# SHEET3.net
KiCad netlist of a schematic drawn in Altium Designer
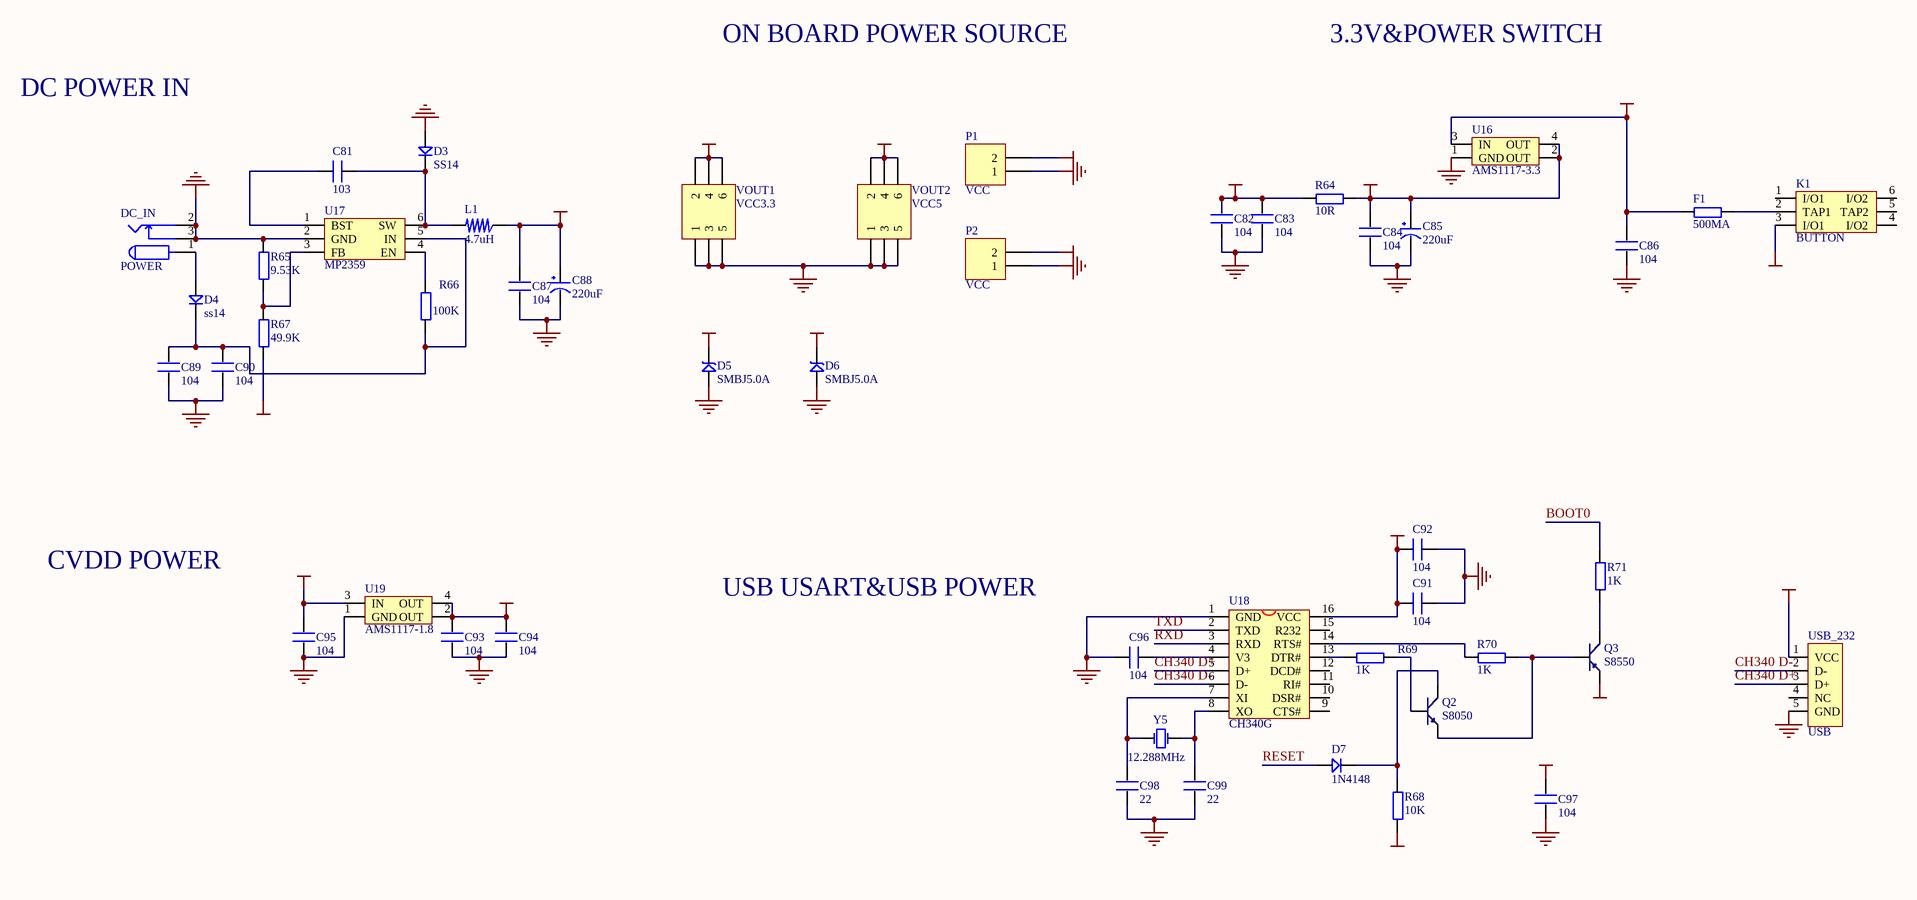
[diagram p0: SHEET3.SCHDOC]

(export (version "E")
  (design (tool "Eeschema 10.0.6"))
  (components
    (comp (ref "C81") (value "103") (footprint "0603P") (libsource (lib "战舰STM32开发板底板封装库") (part "C")))
    (comp (ref "C82") (value "104") (footprint "0603P") (libsource (lib "战舰STM32开发板底板封装库") (part "C")))
    (comp (ref "C83") (value "104") (footprint "0603P") (libsource (lib "战舰STM32开发板底板封装库") (part "C")))
    (comp (ref "C84") (value "104") (footprint "0603P") (libsource (lib "战舰STM32开发板底板封装库") (part "C")))
    (comp (ref "C85") (value "220uF") (footprint "CC6.56.5") (libsource (lib "战舰STM32开发板底板封装库") (part "CAP")))
    (comp (ref "C86") (value "104") (footprint "0603P") (libsource (lib "战舰STM32开发板底板封装库") (part "C")))
    (comp (ref "C87") (value "104") (footprint "0603P") (libsource (lib "战舰STM32开发板底板封装库") (part "C")))
    (comp (ref "C88") (value "220uF") (footprint "CC6.56.5") (libsource (lib "战舰STM32开发板底板封装库") (part "CAP")))
    (comp (ref "C89") (value "104") (footprint "0603P") (libsource (lib "战舰STM32开发板底板封装库") (part "C")))
    (comp (ref "C90") (value "104") (footprint "0603P") (libsource (lib "战舰STM32开发板底板封装库") (part "C")))
    (comp (ref "C91") (value "104") (footprint "0603P") (libsource (lib "战舰STM32开发板底板封装库") (part "C")))
    (comp (ref "C92") (value "104") (footprint "0603P") (libsource (lib "战舰STM32开发板底板封装库") (part "C")))
    (comp (ref "C93") (value "104") (footprint "0603P") (libsource (lib "战舰STM32开发板底板封装库") (part "C")))
    (comp (ref "C94") (value "104") (footprint "0603P") (libsource (lib "战舰STM32开发板底板封装库") (part "C")))
    (comp (ref "C95") (value "104") (footprint "0603P") (libsource (lib "战舰STM32开发板底板封装库") (part "C")))
    (comp (ref "C96") (value "104") (footprint "0603P") (libsource (lib "战舰STM32开发板底板封装库") (part "C")))
    (comp (ref "C97") (value "104") (footprint "0603P") (libsource (lib "战舰STM32开发板底板封装库") (part "C")))
    (comp (ref "C98") (value "22") (footprint "0603P") (libsource (lib "战舰STM32开发板底板封装库") (part "C")))
    (comp (ref "C99") (value "22") (footprint "0603P") (libsource (lib "战舰STM32开发板底板封装库") (part "C")))
    (comp (ref "D3") (value "SS14") (footprint "DIODE_SOP") (libsource (lib "战舰STM32开发板底板封装库") (part "D")))
    (comp (ref "D4") (value "ss14") (footprint "DIODE_SOP") (libsource (lib "战舰STM32开发板底板封装库") (part "D")))
    (comp (ref "D5")
      (value "SMBJ5.0A")
      (footprint "SMBJ")
      (description "TVS")
      (libsource (lib "战舰STM32开发板底板封装库") (part "SMBJ"))
    )
    (comp (ref "D6")
      (value "SMBJ5.0A")
      (footprint "SMBJ")
      (description "TVS")
      (libsource (lib "战舰STM32开发板底板封装库") (part "SMBJ"))
    )
    (comp (ref "D7") (value "1N4148") (footprint "DIODE_SOP") (libsource (lib "战舰STM32开发板底板封装库") (part "D")))
    (comp (ref "DC_IN") (value "POWER") (footprint "DC10B") (libsource (lib "战舰STM32开发板底板封装库") (part "POW")))
    (comp (ref "F1") (value "500MA") (footprint "0805") (libsource (lib "战舰STM32开发板底板封装库") (part "R")))
    (comp (ref "K1")
      (value "BUTTON")
      (footprint "BTN8.5*8.5")
      (libsource (lib "战舰STM32开发板底板封装库") (part "BUTTON"))
    )
    (comp (ref "L1") (value "4.7uH") (footprint "L_SOP74") (libsource (lib "战舰STM32开发板底板封装库") (part "L_SOP")))
    (comp (ref "P1")
      (value "VCC")
      (footprint "HDR1X2")
      (description "Header, 2-Pin")
      (fields (field (name "PUBLISHER") "Altium Limited"))
      (libsource (lib "ZD-STM32-ZOUYU") (part "Header 2"))
    )
    (comp (ref "P2")
      (value "VCC")
      (footprint "HDR1X2")
      (description "Header, 2-Pin")
      (fields (field (name "PUBLISHER") "Altium Limited"))
      (libsource (lib "ZD-STM32-ZOUYU") (part "Header 2"))
    )
    (comp (ref "Q2")
      (value "S8050")
      (footprint "SOT-23R")
      (description "8050/BCW846/BCW847")
      (libsource (lib "战舰STM32开发板底板封装库") (part "NPN"))
    )
    (comp (ref "Q3")
      (value "S8550")
      (footprint "SOT-23R")
      (description "8550/BCW68")
      (libsource (lib "战舰STM32开发板底板封装库") (part "PNP"))
    )
    (comp (ref "R64") (value "10R") (footprint "0603P") (libsource (lib "战舰STM32开发板底板封装库") (part "R")))
    (comp (ref "R65") (value "9.53K") (footprint "0603P") (libsource (lib "战舰STM32开发板底板封装库") (part "R")))
    (comp (ref "R66") (value "100K") (footprint "0603P") (libsource (lib "战舰STM32开发板底板封装库") (part "R")))
    (comp (ref "R67") (value "49.9K") (footprint "0603P") (libsource (lib "战舰STM32开发板底板封装库") (part "R")))
    (comp (ref "R68") (value "10K") (footprint "0603P") (libsource (lib "战舰STM32开发板底板封装库") (part "R")))
    (comp (ref "R69") (value "1K") (footprint "0603P") (libsource (lib "战舰STM32开发板底板封装库") (part "R")))
    (comp (ref "R70") (value "1K") (footprint "0603P") (libsource (lib "战舰STM32开发板底板封装库") (part "R")))
    (comp (ref "R71") (value "1K") (footprint "0603P") (libsource (lib "战舰STM32开发板底板封装库") (part "R")))
    (comp (ref "U16")
      (value "AMS1117-3.3")
      (footprint "AMS1117")
      (libsource (lib "战舰STM32开发板底板封装库") (part "AMS1117"))
    )
    (comp (ref "U17")
      (value "MP2359")
      (footprint "SOT-23-6")
      (description "DC DC Step Down IC")
      (libsource (lib "战舰STM32开发板底板封装库") (part "MP2359"))
    )
    (comp (ref "U18")
      (value "CH340G")
      (footprint "SOP16M")
      (description "USB2UART")
      (libsource (lib "战舰STM32开发板底板封装库") (part "CH340G"))
    )
    (comp (ref "U19")
      (value "AMS1117-1.8")
      (footprint "AMS1117")
      (libsource (lib "战舰STM32开发板底板封装库") (part "AMS1117"))
    )
    (comp (ref "USB_232")
      (value "USB")
      (footprint "USB/SM0.8-6H5")
      (libsource (lib "战舰STM32开发板底板封装库") (part "USB5"))
    )
    (comp (ref "VOUT1")
      (value "VCC3.3")
      (footprint "HDR2X3")
      (description "Header, 3-Pin, Dual row")
      (fields (field (name "PUBLISHER") "Altium Limited"))
      (libsource (lib "战舰STM32开发板底板封装库") (part "Header 3X2"))
    )
    (comp (ref "VOUT2")
      (value "VCC5")
      (footprint "HDR2X3")
      (description "Header, 3-Pin, Dual row")
      (fields (field (name "PUBLISHER") "Altium Limited"))
      (libsource (lib "战舰STM32开发板底板封装库") (part "Header 3X2"))
    )
    (comp (ref "Y5")
      (value "12.288MHz")
      (footprint "XTAL_US")
      (description "Crystal Oscillator")
      (fields (field (name "PUBLISHER") "Altium Limited"))
      (libsource (lib "战舰STM32开发板底板封装库") (part "XTAL_2"))
    )
  )
  (nets
    (net (code "1") (name "/BOOT0") (class "Default") (node (ref "R71") (pin "2") (pintype "passive")))
    (net (code "2") (name "/CH340 D+") (class "Default")
      (node (ref "U18") (pin "5") (pinfunction "D+_5") (pintype "passive"))
      (node (ref "USB_232") (pin "3") (pinfunction "D+_3") (pintype "passive"))
    )
    (net (code "3") (name "/CH340 D-") (class "Default")
      (node (ref "U18") (pin "6") (pinfunction "D-_6") (pintype "passive"))
      (node (ref "USB_232") (pin "2") (pinfunction "D-_2") (pintype "passive"))
    )
    (net (code "4") (name "/RESET") (class "Default") (node (ref "D7") (pin "1") (pintype "passive")))
    (net (code "5") (name "/RXD") (class "Default")
      (node (ref "U18") (pin "3") (pinfunction "RXD_3") (pintype "passive"))
    )
    (net (code "6") (name "/TXD") (class "Default")
      (node (ref "U18") (pin "2") (pinfunction "TXD_2") (pintype "passive"))
    )
    (net (code "7") (name "AVDD") (class "Default")
      (node (ref "C82") (pin "2") (pintype "passive"))
      (node (ref "C83") (pin "2") (pintype "passive"))
      (node (ref "R64") (pin "1") (pintype "passive"))
    )
    (net (code "8") (name "CVDD") (class "Default")
      (node (ref "C93") (pin "2") (pintype "passive"))
      (node (ref "C94") (pin "2") (pintype "passive"))
      (node (ref "U19") (pin "2") (pinfunction "OUT_2") (pintype "passive"))
      (node (ref "U19") (pin "4") (pinfunction "OUT_4") (pintype "passive"))
    )
    (net (code "9") (name "GND") (class "Default")
      (node (ref "C82") (pin "1") (pintype "passive"))
      (node (ref "C83") (pin "1") (pintype "passive"))
      (node (ref "C84") (pin "1") (pintype "passive"))
      (node (ref "C85") (pin "2") (pinfunction "GND_2") (pintype "passive"))
      (node (ref "C86") (pin "1") (pintype "passive"))
      (node (ref "C87") (pin "1") (pintype "passive"))
      (node (ref "C88") (pin "2") (pinfunction "GND_2") (pintype "passive"))
      (node (ref "C89") (pin "1") (pintype "passive"))
      (node (ref "C90") (pin "1") (pintype "passive"))
      (node (ref "C91") (pin "2") (pintype "passive"))
      (node (ref "C92") (pin "2") (pintype "passive"))
      (node (ref "C93") (pin "1") (pintype "passive"))
      (node (ref "C94") (pin "1") (pintype "passive"))
      (node (ref "C95") (pin "1") (pintype "passive"))
      (node (ref "C96") (pin "1") (pintype "passive"))
      (node (ref "C97") (pin "1") (pintype "passive"))
      (node (ref "C98") (pin "1") (pintype "passive"))
      (node (ref "C99") (pin "1") (pintype "passive"))
      (node (ref "D3") (pin "1") (pintype "passive"))
      (node (ref "D5") (pin "1") (pintype "passive"))
      (node (ref "D6") (pin "1") (pintype "passive"))
      (node (ref "DC_IN") (pin "2") (pintype "passive"))
      (node (ref "DC_IN") (pin "3") (pintype "passive"))
      (node (ref "P1") (pin "1") (pinfunction "1_1") (pintype "passive"))
      (node (ref "P2") (pin "1") (pinfunction "1_1") (pintype "passive"))
      (node (ref "R65") (pin "2") (pintype "passive"))
      (node (ref "U16") (pin "1") (pinfunction "GND_1") (pintype "passive"))
      (node (ref "U17") (pin "2") (pinfunction "GND_2") (pintype "passive"))
      (node (ref "U18") (pin "1") (pinfunction "GND_1") (pintype "passive"))
      (node (ref "U19") (pin "1") (pinfunction "GND_1") (pintype "passive"))
      (node (ref "USB_232") (pin "5") (pinfunction "GND_5") (pintype "passive"))
      (node (ref "VOUT1") (pin "1") (pinfunction "1_1") (pintype "passive"))
      (node (ref "VOUT1") (pin "3") (pinfunction "3_3") (pintype "passive"))
      (node (ref "VOUT1") (pin "5") (pinfunction "5_5") (pintype "passive"))
      (node (ref "VOUT2") (pin "1") (pinfunction "1_1") (pintype "passive"))
      (node (ref "VOUT2") (pin "3") (pinfunction "3_3") (pintype "passive"))
      (node (ref "VOUT2") (pin "5") (pinfunction "5_5") (pintype "passive"))
    )
    (net (code "10") (name "Net-(D4-Pad1)") (class "Default")
      (node (ref "D4") (pin "1") (pintype "passive"))
      (node (ref "DC_IN") (pin "1") (pintype "passive"))
    )
    (net (code "11") (name "Net-(K1-TAP1)") (class "Default")
      (node (ref "F1") (pin "2") (pintype "passive"))
      (node (ref "K1") (pin "2") (pinfunction "TAP1_2") (pintype "passive"))
    )
    (net (code "12") (name "Net-(Q2-B)") (class "Default")
      (node (ref "Q2") (pin "2") (pinfunction "B_2") (pintype "passive"))
      (node (ref "R69") (pin "2") (pintype "passive"))
    )
    (net (code "13") (name "Net-(Q2-C)") (class "Default")
      (node (ref "D7") (pin "2") (pintype "passive"))
      (node (ref "Q2") (pin "3") (pinfunction "C_3") (pintype "passive"))
      (node (ref "R68") (pin "2") (pintype "passive"))
    )
    (net (code "14") (name "Net-(Q2-E)") (class "Default")
      (node (ref "Q2") (pin "1") (pinfunction "E_1") (pintype "passive"))
      (node (ref "Q3") (pin "2") (pinfunction "B_2") (pintype "passive"))
      (node (ref "R70") (pin "2") (pintype "passive"))
    )
    (net (code "15") (name "Net-(Q3-C)") (class "Default")
      (node (ref "Q3") (pin "3") (pinfunction "C_3") (pintype "passive"))
      (node (ref "R71") (pin "1") (pintype "passive"))
    )
    (net (code "16") (name "Net-(U17-BST)") (class "Default")
      (node (ref "C81") (pin "1") (pintype "passive"))
      (node (ref "U17") (pin "1") (pinfunction "BST_1") (pintype "passive"))
    )
    (net (code "17") (name "Net-(U17-EN)") (class "Default")
      (node (ref "R66") (pin "2") (pintype "passive"))
      (node (ref "U17") (pin "4") (pinfunction "EN_4") (pintype "passive"))
    )
    (net (code "18") (name "Net-(U17-FB)") (class "Default")
      (node (ref "R65") (pin "1") (pintype "passive"))
      (node (ref "R67") (pin "2") (pintype "passive"))
      (node (ref "U17") (pin "3") (pinfunction "FB_3") (pintype "passive"))
    )
    (net (code "19") (name "Net-(U17-IN)") (class "Default")
      (node (ref "C89") (pin "2") (pintype "passive"))
      (node (ref "C90") (pin "2") (pintype "passive"))
      (node (ref "D4") (pin "2") (pintype "passive"))
      (node (ref "R66") (pin "1") (pintype "passive"))
      (node (ref "U17") (pin "5") (pinfunction "IN_5") (pintype "passive"))
    )
    (net (code "20") (name "Net-(U17-SW)") (class "Default")
      (node (ref "C81") (pin "2") (pintype "passive"))
      (node (ref "D3") (pin "2") (pintype "passive"))
      (node (ref "L1") (pin "2") (pinfunction "2_2") (pintype "passive"))
      (node (ref "U17") (pin "6") (pinfunction "SW_6") (pintype "passive"))
    )
    (net (code "21") (name "Net-(U18-DTR#)") (class "Default")
      (node (ref "R69") (pin "1") (pintype "passive"))
      (node (ref "U18") (pin "13") (pinfunction "DTR#_13") (pintype "passive"))
    )
    (net (code "22") (name "Net-(U18-RTS#)") (class "Default")
      (node (ref "R70") (pin "1") (pintype "passive"))
      (node (ref "U18") (pin "14") (pinfunction "RTS#_14") (pintype "passive"))
    )
    (net (code "23") (name "Net-(U18-V3)") (class "Default")
      (node (ref "C96") (pin "2") (pintype "passive"))
      (node (ref "U18") (pin "4") (pinfunction "V3_4") (pintype "passive"))
    )
    (net (code "24") (name "Net-(U18-XI)") (class "Default")
      (node (ref "C98") (pin "2") (pintype "passive"))
      (node (ref "U18") (pin "7") (pinfunction "XI_7") (pintype "passive"))
      (node (ref "Y5") (pin "1") (pinfunction "OSC1_1") (pintype "passive"))
    )
    (net (code "25") (name "Net-(U18-XO)") (class "Default")
      (node (ref "C99") (pin "2") (pintype "passive"))
      (node (ref "U18") (pin "8") (pinfunction "XO_8") (pintype "passive"))
      (node (ref "Y5") (pin "2") (pinfunction "OSC2_2") (pintype "passive"))
    )
    (net (code "26") (name "VCC3.3") (class "Default")
      (node (ref "C84") (pin "2") (pintype "passive"))
      (node (ref "C85") (pin "1") (pinfunction "VCC_1") (pintype "passive"))
      (node (ref "D6") (pin "2") (pintype "passive"))
      (node (ref "Q3") (pin "1") (pinfunction "E_1") (pintype "passive"))
      (node (ref "R64") (pin "2") (pintype "passive"))
      (node (ref "R68") (pin "1") (pintype "passive"))
      (node (ref "U16") (pin "2") (pinfunction "OUT_2") (pintype "passive"))
      (node (ref "U16") (pin "4") (pinfunction "OUT_4") (pintype "passive"))
      (node (ref "VOUT1") (pin "2") (pinfunction "2_2") (pintype "passive"))
      (node (ref "VOUT1") (pin "4") (pinfunction "4_4") (pintype "passive"))
      (node (ref "VOUT1") (pin "6") (pinfunction "6_6") (pintype "passive"))
    )
    (net (code "27") (name "VCC5") (class "Default")
      (node (ref "C86") (pin "2") (pintype "passive"))
      (node (ref "C91") (pin "1") (pintype "passive"))
      (node (ref "C92") (pin "1") (pintype "passive"))
      (node (ref "C95") (pin "2") (pintype "passive"))
      (node (ref "C97") (pin "2") (pintype "passive"))
      (node (ref "D5") (pin "2") (pintype "passive"))
      (node (ref "F1") (pin "1") (pintype "passive"))
      (node (ref "P1") (pin "2") (pinfunction "2_2") (pintype "passive"))
      (node (ref "P2") (pin "2") (pinfunction "2_2") (pintype "passive"))
      (node (ref "U16") (pin "3") (pinfunction "IN_3") (pintype "passive"))
      (node (ref "U18") (pin "16") (pinfunction "VCC_16") (pintype "passive"))
      (node (ref "U19") (pin "3") (pinfunction "IN_3") (pintype "passive"))
      (node (ref "VOUT2") (pin "2") (pinfunction "2_2") (pintype "passive"))
      (node (ref "VOUT2") (pin "4") (pinfunction "4_4") (pintype "passive"))
      (node (ref "VOUT2") (pin "6") (pinfunction "6_6") (pintype "passive"))
    )
    (net (code "28") (name "VUSB") (class "Default")
      (node (ref "C87") (pin "2") (pintype "passive"))
      (node (ref "C88") (pin "1") (pinfunction "VCC_1") (pintype "passive"))
      (node (ref "K1") (pin "3") (pinfunction "I/O1_3") (pintype "passive"))
      (node (ref "L1") (pin "1") (pinfunction "1_1") (pintype "passive"))
      (node (ref "R67") (pin "1") (pintype "passive"))
      (node (ref "USB_232") (pin "1") (pinfunction "VCC_1") (pintype "passive"))
    )
    (net (code "29") (name "unconnected-(K1-I{slash}O1-Pad1)") (class "Default")
      (node (ref "K1") (pin "1") (pinfunction "I/O1_1") (pintype "passive"))
    )
    (net (code "30") (name "unconnected-(K1-I{slash}O2-Pad4)") (class "Default")
      (node (ref "K1") (pin "4") (pinfunction "I/O2_4") (pintype "passive"))
    )
    (net (code "31") (name "unconnected-(K1-I{slash}O2-Pad6)") (class "Default")
      (node (ref "K1") (pin "6") (pinfunction "I/O2_6") (pintype "passive"))
    )
    (net (code "32") (name "unconnected-(K1-TAP2-Pad5)") (class "Default")
      (node (ref "K1") (pin "5") (pinfunction "TAP2_5") (pintype "passive"))
    )
    (net (code "33") (name "unconnected-(U18-CTS#-Pad9)") (class "Default")
      (node (ref "U18") (pin "9") (pinfunction "CTS#_9") (pintype "passive"))
    )
    (net (code "34") (name "unconnected-(U18-DCD#-Pad12)") (class "Default")
      (node (ref "U18") (pin "12") (pinfunction "DCD#_12") (pintype "passive"))
    )
    (net (code "35") (name "unconnected-(U18-DSR#-Pad10)") (class "Default")
      (node (ref "U18") (pin "10") (pinfunction "DSR#_10") (pintype "passive"))
    )
    (net (code "36") (name "unconnected-(U18-R232-Pad15)") (class "Default")
      (node (ref "U18") (pin "15") (pinfunction "R232_15") (pintype "passive"))
    )
    (net (code "37") (name "unconnected-(U18-RI#-Pad11)") (class "Default")
      (node (ref "U18") (pin "11") (pinfunction "RI#_11") (pintype "passive"))
    )
    (net (code "38") (name "unconnected-(USB_232-NC-Pad4)") (class "Default")
      (node (ref "USB_232") (pin "4") (pinfunction "NC_4") (pintype "passive"))
    )
  )
)
